# one_Mhz.net
KiCad netlist of a schematic drawn in EAGLE
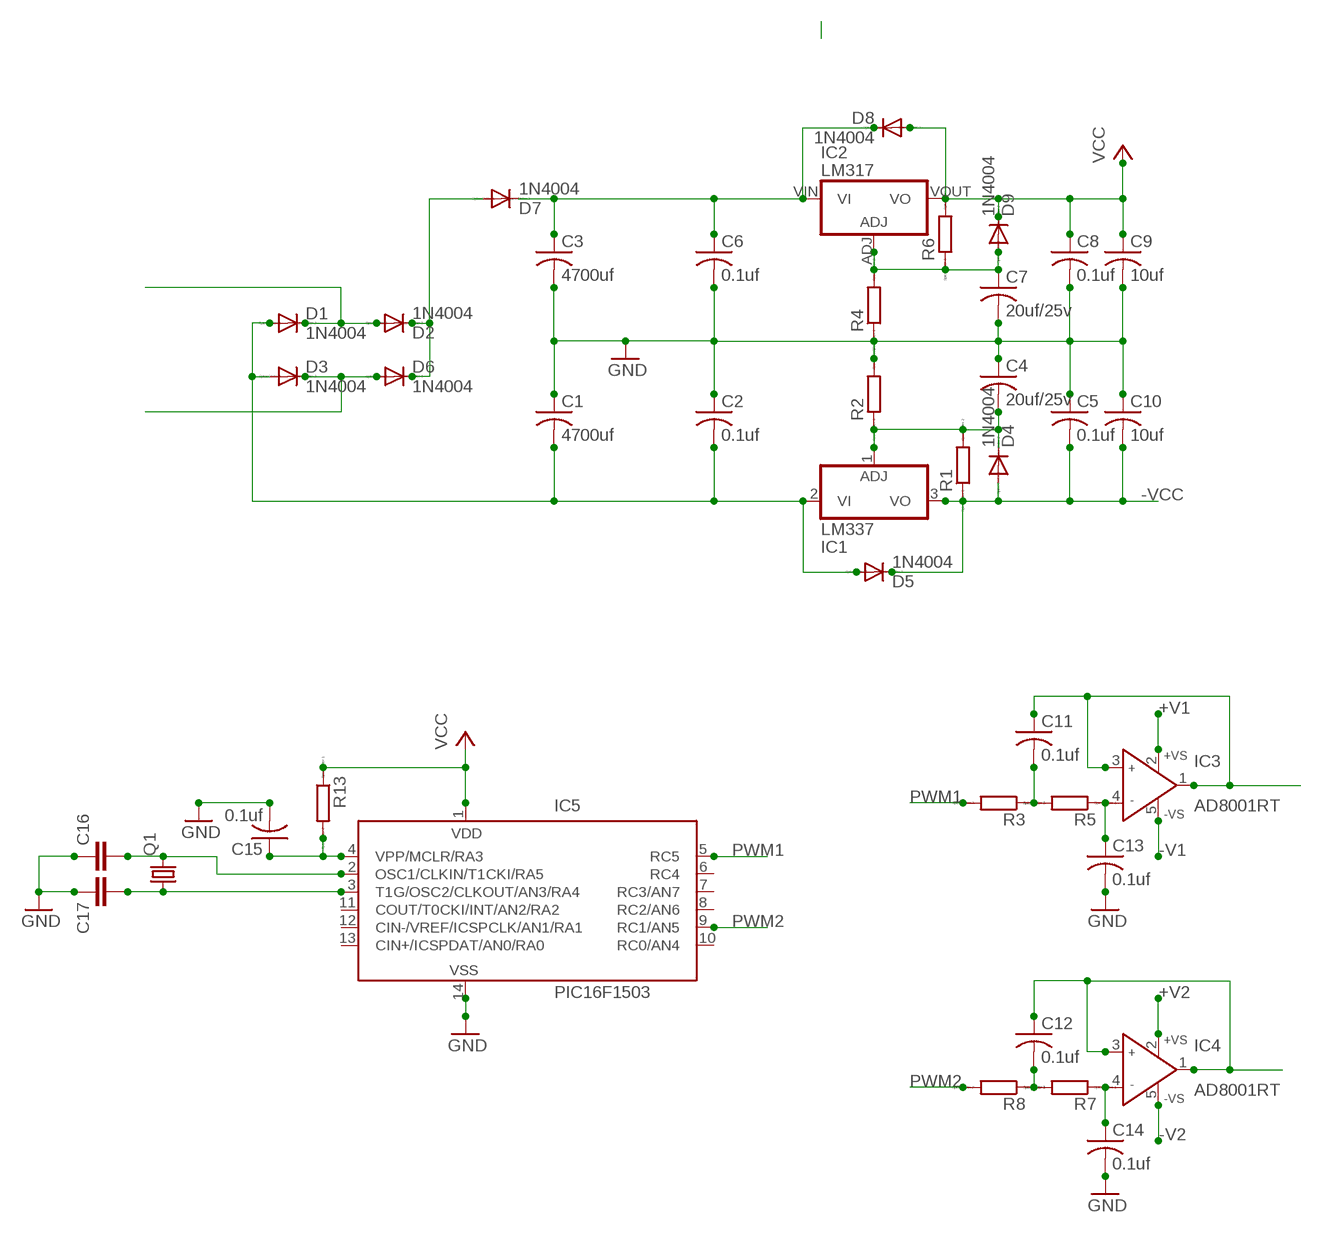
[diagram p0: schematic, sheet 1]

(export (version "E")
  (design (tool "Eeschema 10.0.6"))
  (components
    (comp (ref "C1")
      (value "4700uf")
      (footprint "eagle-import:C025-025X050")
      (libsource (lib "eagle-import") (part "C-US025-025X050"))
    )
    (comp (ref "C2")
      (value "0.1uf")
      (footprint "eagle-import:C025-025X050")
      (libsource (lib "eagle-import") (part "C-US025-025X050"))
    )
    (comp (ref "C3")
      (value "4700uf")
      (footprint "eagle-import:C025-025X050")
      (libsource (lib "eagle-import") (part "C-US025-025X050"))
    )
    (comp (ref "C4")
      (value "20uf/25v")
      (footprint "eagle-import:C025-025X050")
      (libsource (lib "eagle-import") (part "C-US025-025X050"))
    )
    (comp (ref "C5")
      (value "0.1uf")
      (footprint "eagle-import:C025-025X050")
      (libsource (lib "eagle-import") (part "C-US025-025X050"))
    )
    (comp (ref "C6")
      (value "0.1uf")
      (footprint "eagle-import:C025-025X050")
      (libsource (lib "eagle-import") (part "C-US025-025X050"))
    )
    (comp (ref "C7")
      (value "20uf/25v")
      (footprint "eagle-import:C025-025X050")
      (libsource (lib "eagle-import") (part "C-US025-025X050"))
    )
    (comp (ref "C8")
      (value "0.1uf")
      (footprint "eagle-import:C025-025X050")
      (libsource (lib "eagle-import") (part "C-US025-025X050"))
    )
    (comp (ref "C9")
      (value "10uf")
      (footprint "eagle-import:C025-025X050")
      (libsource (lib "eagle-import") (part "C-US025-025X050"))
    )
    (comp (ref "C10")
      (value "10uf")
      (footprint "eagle-import:C025-025X050")
      (libsource (lib "eagle-import") (part "C-US025-025X050"))
    )
    (comp (ref "C11")
      (value "0.1uf")
      (footprint "eagle-import:C025-025X050")
      (libsource (lib "eagle-import") (part "C-US025-025X050"))
    )
    (comp (ref "C12")
      (value "0.1uf")
      (footprint "eagle-import:C025-025X050")
      (libsource (lib "eagle-import") (part "C-US025-025X050"))
    )
    (comp (ref "C13")
      (value "0.1uf")
      (footprint "eagle-import:C025-025X050")
      (libsource (lib "eagle-import") (part "C-US025-025X050"))
    )
    (comp (ref "C14")
      (value "0.1uf")
      (footprint "eagle-import:C025-025X050")
      (libsource (lib "eagle-import") (part "C-US025-025X050"))
    )
    (comp (ref "C15")
      (value "0.1uf")
      (footprint "eagle-import:C025-025X050")
      (libsource (lib "eagle-import") (part "C-US025-025X050"))
    )
    (comp (ref "C16")
      (value "C2,5-3")
      (footprint "eagle-import:C2.5-3")
      (libsource (lib "eagle-import") (part "C2,5-3"))
    )
    (comp (ref "C17")
      (value "C2,5-3")
      (footprint "eagle-import:C2.5-3")
      (libsource (lib "eagle-import") (part "C2,5-3"))
    )
    (comp (ref "D1")
      (value "1N4004")
      (footprint "eagle-import:DO41-10")
      (libsource (lib "eagle-import") (part "1N4004"))
    )
    (comp (ref "D2")
      (value "1N4004")
      (footprint "eagle-import:DO41-10")
      (libsource (lib "eagle-import") (part "1N4004"))
    )
    (comp (ref "D3")
      (value "1N4004")
      (footprint "eagle-import:DO41-10")
      (libsource (lib "eagle-import") (part "1N4004"))
    )
    (comp (ref "D4")
      (value "1N4004")
      (footprint "eagle-import:DO41-10")
      (libsource (lib "eagle-import") (part "1N4004"))
    )
    (comp (ref "D5")
      (value "1N4004")
      (footprint "eagle-import:DO41-10")
      (libsource (lib "eagle-import") (part "1N4004"))
    )
    (comp (ref "D6")
      (value "1N4004")
      (footprint "eagle-import:DO41-10")
      (libsource (lib "eagle-import") (part "1N4004"))
    )
    (comp (ref "D7")
      (value "1N4004")
      (footprint "eagle-import:DO41-10")
      (libsource (lib "eagle-import") (part "1N4004"))
    )
    (comp (ref "D8")
      (value "1N4004")
      (footprint "eagle-import:DO41-10")
      (libsource (lib "eagle-import") (part "1N4004"))
    )
    (comp (ref "D9")
      (value "1N4004")
      (footprint "eagle-import:DO41-10")
      (libsource (lib "eagle-import") (part "1N4004"))
    )
    (comp (ref "IC1")
      (value "LM337")
      (footprint "eagle-import:TO220V")
      (libsource (lib "eagle-import") (part "78TV8"))
    )
    (comp (ref "IC2")
      (value "LM317")
      (footprint "eagle-import:DPACK")
      (libsource (lib "eagle-import") (part "317"))
    )
    (comp (ref "IC3")
      (value "AD8001RT")
      (footprint "eagle-import:SOT23-5")
      (fields (field (name "MF") "ALTERA CORPORATION") (field (name "MPN") "AD8001ARTZ-REEL7"))
      (libsource (lib "eagle-import") (part "AD8001RT"))
    )
    (comp (ref "IC4")
      (value "AD8001RT")
      (footprint "eagle-import:SOT23-5")
      (fields (field (name "MF") "ALTERA CORPORATION") (field (name "MPN") "AD8001ARTZ-REEL7"))
      (libsource (lib "eagle-import") (part "AD8001RT"))
    )
    (comp (ref "IC5")
      (value "PIC16F1503")
      (footprint "eagle-import:DIL14")
      (fields (field (name "MF") "MICROCHIP") (field (name "MPN") "PIC16F676-I/P"))
      (libsource (lib "eagle-import") (part "PIC16F676P"))
    )
    (comp (ref "Q1")
      (value "CRYSTALHC49U-V")
      (footprint "eagle-import:HC49U-V")
      (libsource (lib "eagle-import") (part "CRYSTALHC49U-V"))
    )
    (comp (ref "R1")
      (value "R0207/10")
      (footprint "eagle-import:0207_10")
      (libsource (lib "eagle-import") (part "R0207/10"))
    )
    (comp (ref "R2")
      (value "R0207/10")
      (footprint "eagle-import:0207_10")
      (libsource (lib "eagle-import") (part "R0207/10"))
    )
    (comp (ref "R3")
      (value "R0207/10")
      (footprint "eagle-import:0207_10")
      (libsource (lib "eagle-import") (part "R0207/10"))
    )
    (comp (ref "R4")
      (value "R0207/10")
      (footprint "eagle-import:0207_10")
      (libsource (lib "eagle-import") (part "R0207/10"))
    )
    (comp (ref "R5")
      (value "R0207/10")
      (footprint "eagle-import:0207_10")
      (libsource (lib "eagle-import") (part "R0207/10"))
    )
    (comp (ref "R6")
      (value "R0207/10")
      (footprint "eagle-import:0207_10")
      (libsource (lib "eagle-import") (part "R0207/10"))
    )
    (comp (ref "R7")
      (value "R0207/10")
      (footprint "eagle-import:0207_10")
      (libsource (lib "eagle-import") (part "R0207/10"))
    )
    (comp (ref "R8")
      (value "R0207/10")
      (footprint "eagle-import:0207_10")
      (libsource (lib "eagle-import") (part "R0207/10"))
    )
    (comp (ref "R13")
      (value "R0207/10")
      (footprint "eagle-import:0207_10")
      (libsource (lib "eagle-import") (part "R0207/10"))
    )
  )
  (nets
    (net (code "1") (name "/+V1") (class "Default")
      (node (ref "IC3") (pin "2") (pinfunction "+VS_2") (pintype "input"))
    )
    (net (code "2") (name "/+V2") (class "Default")
      (node (ref "IC4") (pin "2") (pinfunction "+VS_2") (pintype "input"))
    )
    (net (code "3") (name "/-V1") (class "Default")
      (node (ref "IC3") (pin "5") (pinfunction "-VS_5") (pintype "input"))
    )
    (net (code "4") (name "/-V2") (class "Default")
      (node (ref "IC4") (pin "5") (pinfunction "-VS_5") (pintype "input"))
    )
    (net (code "5") (name "/-VCC") (class "Default")
      (node (ref "C10") (pin "2") (pinfunction "2_2") (pintype "passive"))
      (node (ref "C5") (pin "2") (pinfunction "2_2") (pintype "passive"))
      (node (ref "D4") (pin "A") (pinfunction "A_A") (pintype "passive"))
      (node (ref "D5") (pin "C") (pinfunction "C_C") (pintype "passive"))
      (node (ref "IC1") (pin "3") (pinfunction "VO_3") (pintype "passive"))
      (node (ref "R1") (pin "1") (pinfunction "1_1") (pintype "passive"))
    )
    (net (code "6") (name "/PWM1") (class "Default")
      (node (ref "IC5") (pin "5") (pinfunction "RC5_5") (pintype "bidirectional"))
      (node (ref "R3") (pin "2") (pinfunction "2_2") (pintype "passive"))
    )
    (net (code "7") (name "/PWM2") (class "Default")
      (node (ref "IC5") (pin "9") (pinfunction "RC1/AN5_9") (pintype "bidirectional"))
      (node (ref "R8") (pin "2") (pinfunction "2_2") (pintype "passive"))
    )
    (net (code "8") (name "GND") (class "Default")
      (node (ref "C1") (pin "1") (pinfunction "1_1") (pintype "passive"))
      (node (ref "C10") (pin "1") (pinfunction "1_1") (pintype "passive"))
      (node (ref "C13") (pin "2") (pinfunction "2_2") (pintype "passive"))
      (node (ref "C14") (pin "2") (pinfunction "2_2") (pintype "passive"))
      (node (ref "C15") (pin "2") (pinfunction "2_2") (pintype "passive"))
      (node (ref "C16") (pin "1") (pinfunction "1_1") (pintype "passive"))
      (node (ref "C17") (pin "1") (pinfunction "1_1") (pintype "passive"))
      (node (ref "C2") (pin "1") (pinfunction "1_1") (pintype "passive"))
      (node (ref "C3") (pin "2") (pinfunction "2_2") (pintype "passive"))
      (node (ref "C4") (pin "1") (pinfunction "1_1") (pintype "passive"))
      (node (ref "C5") (pin "1") (pinfunction "1_1") (pintype "passive"))
      (node (ref "C6") (pin "2") (pinfunction "2_2") (pintype "passive"))
      (node (ref "C7") (pin "2") (pinfunction "2_2") (pintype "passive"))
      (node (ref "C8") (pin "2") (pinfunction "2_2") (pintype "passive"))
      (node (ref "C9") (pin "2") (pinfunction "2_2") (pintype "passive"))
      (node (ref "IC5") (pin "14") (pinfunction "VSS_14") (pintype "power_in"))
      (node (ref "R2") (pin "2") (pinfunction "2_2") (pintype "passive"))
      (node (ref "R4") (pin "1") (pinfunction "1_1") (pintype "passive"))
    )
    (net (code "9") (name "Net-(C7-Pad1)") (class "Default")
      (node (ref "C7") (pin "1") (pinfunction "1_1") (pintype "passive"))
      (node (ref "D9") (pin "A") (pinfunction "A_A") (pintype "passive"))
      (node (ref "IC2") (pin "ADJ") (pinfunction "ADJ_ADJ") (pintype "input"))
      (node (ref "R4") (pin "2") (pinfunction "2_2") (pintype "passive"))
      (node (ref "R6") (pin "1") (pinfunction "1_1") (pintype "passive"))
    )
    (net (code "10") (name "Net-(C11-Pad2)") (class "Default")
      (node (ref "C11") (pin "2") (pinfunction "2_2") (pintype "passive"))
      (node (ref "R3") (pin "1") (pinfunction "1_1") (pintype "passive"))
      (node (ref "R5") (pin "2") (pinfunction "2_2") (pintype "passive"))
    )
    (net (code "11") (name "Net-(C12-Pad2)") (class "Default")
      (node (ref "C12") (pin "2") (pinfunction "2_2") (pintype "passive"))
      (node (ref "R7") (pin "2") (pinfunction "2_2") (pintype "passive"))
      (node (ref "R8") (pin "1") (pinfunction "1_1") (pintype "passive"))
    )
    (net (code "12") (name "Net-(D1-PadC)") (class "Default")
      (node (ref "D1") (pin "C") (pinfunction "C_C") (pintype "passive"))
      (node (ref "D2") (pin "A") (pinfunction "A_A") (pintype "passive"))
    )
    (net (code "13") (name "Net-(D2-PadC)") (class "Default")
      (node (ref "D2") (pin "C") (pinfunction "C_C") (pintype "passive"))
      (node (ref "D6") (pin "C") (pinfunction "C_C") (pintype "passive"))
      (node (ref "D7") (pin "A") (pinfunction "A_A") (pintype "passive"))
    )
    (net (code "14") (name "Net-(D3-PadC)") (class "Default")
      (node (ref "D3") (pin "C") (pinfunction "C_C") (pintype "passive"))
      (node (ref "D6") (pin "A") (pinfunction "A_A") (pintype "passive"))
    )
    (net (code "15") (name "Net-(IC1-ADJ)") (class "Default")
      (node (ref "C4") (pin "2") (pinfunction "2_2") (pintype "passive"))
      (node (ref "D4") (pin "C") (pinfunction "C_C") (pintype "passive"))
      (node (ref "IC1") (pin "1") (pinfunction "ADJ_1") (pintype "passive"))
      (node (ref "R1") (pin "2") (pinfunction "2_2") (pintype "passive"))
      (node (ref "R2") (pin "1") (pinfunction "1_1") (pintype "passive"))
    )
    (net (code "16") (name "Net-(IC1-VI)") (class "Default")
      (node (ref "C1") (pin "2") (pinfunction "2_2") (pintype "passive"))
      (node (ref "C2") (pin "2") (pinfunction "2_2") (pintype "passive"))
      (node (ref "D1") (pin "A") (pinfunction "A_A") (pintype "passive"))
      (node (ref "D3") (pin "A") (pinfunction "A_A") (pintype "passive"))
      (node (ref "D5") (pin "A") (pinfunction "A_A") (pintype "passive"))
      (node (ref "IC1") (pin "2") (pinfunction "VI_2") (pintype "input"))
    )
    (net (code "17") (name "Net-(IC2-VI)") (class "Default")
      (node (ref "C3") (pin "1") (pinfunction "1_1") (pintype "passive"))
      (node (ref "C6") (pin "1") (pinfunction "1_1") (pintype "passive"))
      (node (ref "D7") (pin "C") (pinfunction "C_C") (pintype "passive"))
      (node (ref "D8") (pin "C") (pinfunction "C_C") (pintype "passive"))
      (node (ref "IC2") (pin "VIN") (pinfunction "VI_VIN") (pintype "input"))
    )
    (net (code "18") (name "Net-(IC3-IN+)") (class "Default")
      (node (ref "C11") (pin "1") (pinfunction "1_1") (pintype "passive"))
      (node (ref "IC3") (pin "1") (pinfunction "OUT_1") (pintype "output"))
      (node (ref "IC3") (pin "3") (pinfunction "IN+_3") (pintype "input"))
    )
    (net (code "19") (name "Net-(IC3-IN-)") (class "Default")
      (node (ref "C13") (pin "1") (pinfunction "1_1") (pintype "passive"))
      (node (ref "IC3") (pin "4") (pinfunction "IN-_4") (pintype "input"))
      (node (ref "R5") (pin "1") (pinfunction "1_1") (pintype "passive"))
    )
    (net (code "20") (name "Net-(IC4-IN+)") (class "Default")
      (node (ref "C12") (pin "1") (pinfunction "1_1") (pintype "passive"))
      (node (ref "IC4") (pin "1") (pinfunction "OUT_1") (pintype "output"))
      (node (ref "IC4") (pin "3") (pinfunction "IN+_3") (pintype "input"))
    )
    (net (code "21") (name "Net-(IC4-IN-)") (class "Default")
      (node (ref "C14") (pin "1") (pinfunction "1_1") (pintype "passive"))
      (node (ref "IC4") (pin "4") (pinfunction "IN-_4") (pintype "input"))
      (node (ref "R7") (pin "1") (pinfunction "1_1") (pintype "passive"))
    )
    (net (code "22") (name "Net-(IC5-OSC1{slash}CLKIN{slash}T1CKI{slash}RA5)") (class "Default")
      (node (ref "C16") (pin "2") (pinfunction "2_2") (pintype "passive"))
      (node (ref "IC5") (pin "2") (pinfunction "OSC1/CLKIN/T1CKI/RA5_2") (pintype "bidirectional"))
      (node (ref "Q1") (pin "2") (pinfunction "2_2") (pintype "passive"))
    )
    (net (code "23") (name "Net-(IC5-T1G{slash}OSC2{slash}CLKOUT{slash}AN3{slash}RA4)") (class "Default")
      (node (ref "C17") (pin "2") (pinfunction "2_2") (pintype "passive"))
      (node (ref "IC5") (pin "3") (pinfunction "T1G/OSC2/CLKOUT/AN3/RA4_3") (pintype "bidirectional"))
      (node (ref "Q1") (pin "1") (pinfunction "1_1") (pintype "passive"))
    )
    (net (code "24") (name "Net-(IC5-VPP{slash}MCLR{slash}RA3)") (class "Default")
      (node (ref "C15") (pin "1") (pinfunction "1_1") (pintype "passive"))
      (node (ref "IC5") (pin "4") (pinfunction "VPP/MCLR/RA3_4") (pintype "input"))
      (node (ref "R13") (pin "2") (pinfunction "2_2") (pintype "passive"))
    )
    (net (code "25") (name "VCC") (class "Default")
      (node (ref "C8") (pin "1") (pinfunction "1_1") (pintype "passive"))
      (node (ref "C9") (pin "1") (pinfunction "1_1") (pintype "passive"))
      (node (ref "D8") (pin "A") (pinfunction "A_A") (pintype "passive"))
      (node (ref "D9") (pin "C") (pinfunction "C_C") (pintype "passive"))
      (node (ref "IC2") (pin "VOUT") (pinfunction "VO_VOUT") (pintype "passive"))
      (node (ref "IC5") (pin "1") (pinfunction "VDD_1") (pintype "power_in"))
      (node (ref "R13") (pin "1") (pinfunction "1_1") (pintype "passive"))
      (node (ref "R6") (pin "2") (pinfunction "2_2") (pintype "passive"))
    )
    (net (code "26") (name "unconnected-(IC5-CIN+{slash}ICSPDAT{slash}AN0{slash}RA0-Pad13)") (class "Default")
      (node (ref "IC5") (pin "13") (pinfunction "CIN+/ICSPDAT/AN0/RA0_13") (pintype "bidirectional"))
    )
    (net (code "27") (name "unconnected-(IC5-CIN-{slash}VREF{slash}ICSPCLK{slash}AN1{slash}RA1-Pad12)") (class "Default")
      (node (ref "IC5") (pin "12") (pinfunction "CIN-/VREF/ICSPCLK/AN1/RA1_12") (pintype "bidirectional"))
    )
    (net (code "28") (name "unconnected-(IC5-COUT{slash}T0CKI{slash}INT{slash}AN2{slash}RA2-Pad11)") (class "Default")
      (node (ref "IC5") (pin "11") (pinfunction "COUT/T0CKI/INT/AN2/RA2_11") (pintype "bidirectional"))
    )
    (net (code "29") (name "unconnected-(IC5-RC0{slash}AN4-Pad10)") (class "Default")
      (node (ref "IC5") (pin "10") (pinfunction "RC0/AN4_10") (pintype "bidirectional"))
    )
    (net (code "30") (name "unconnected-(IC5-RC2{slash}AN6-Pad8)") (class "Default")
      (node (ref "IC5") (pin "8") (pinfunction "RC2/AN6_8") (pintype "bidirectional"))
    )
    (net (code "31") (name "unconnected-(IC5-RC3{slash}AN7-Pad7)") (class "Default")
      (node (ref "IC5") (pin "7") (pinfunction "RC3/AN7_7") (pintype "bidirectional"))
    )
    (net (code "32") (name "unconnected-(IC5-RC4-Pad6)") (class "Default")
      (node (ref "IC5") (pin "6") (pinfunction "RC4_6") (pintype "bidirectional"))
    )
  )
)
